# MCU.net
KiCad netlist of a schematic drawn in Altium Designer
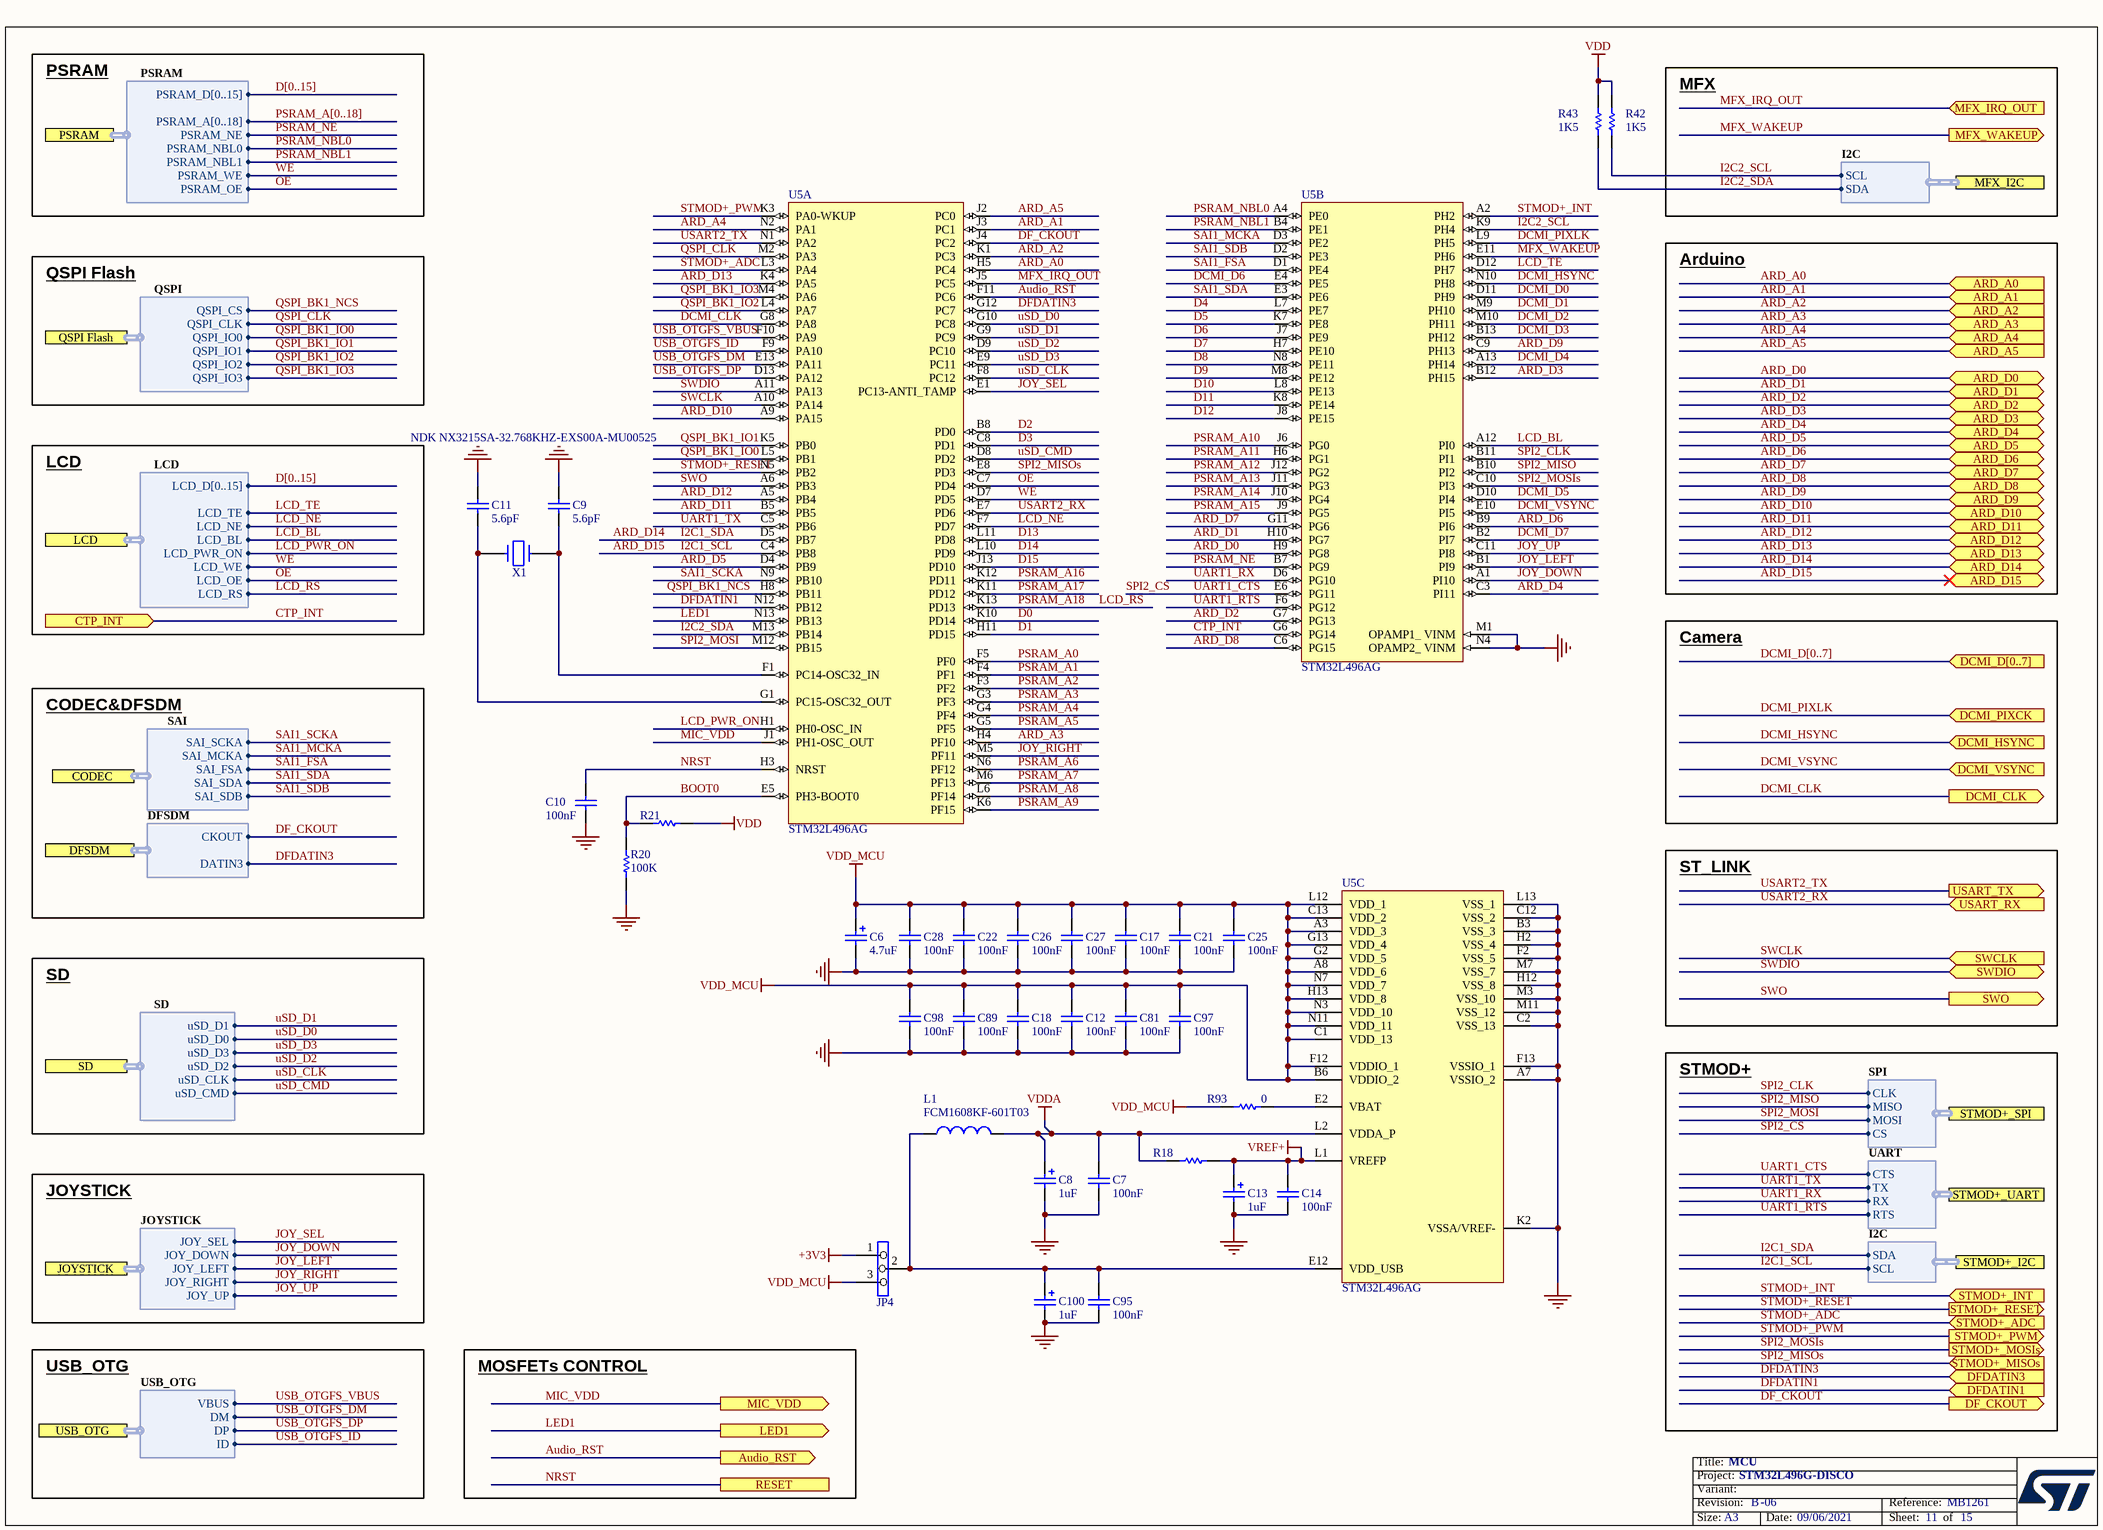
[diagram p0: MCU.SchDoc]

(export (version "E")
  (design (tool "Eeschema 10.0.6"))
  (components
    (comp (ref "C6")
      (value "4.7uF")
      (footprint "TAN-A")
      (description "TAN Capacitor,4.7uF,10%,16V,A Type,AVX")
      (fields (field (name "Comment") "TAJA475K016R") (field (name "PUBLISHER") "Altium Limited"))
      (libsource (lib "Miscellaneous Devices") (part "Cap Pol1"))
    )
    (comp (ref "C7")
      (value "100nF")
      (footprint "0603C")
      (description "Capacitor,100nF,10%,16V,X7R,0603,YAGEO")
      (fields (field (name "Comment") "CC0603KRX7R7BB104") (field (name "PUBLISHER") "Altium Limited"))
      (libsource (lib "Miscellaneous Devices") (part "Cap"))
    )
    (comp (ref "C8")
      (value "1uF")
      (footprint "TAN-A")
      (description "Tan Capacitor,1uF,10%,16V,Tan-A,TAJA105K016R")
      (fields (field (name "Comment") "TAJA105K016R") (field (name "PUBLISHER") "Altium Limited"))
      (libsource (lib "Miscellaneous Devices") (part "Cap Pol1"))
    )
    (comp (ref "C9")
      (value "5.6pF")
      (footprint "0603C")
      (description "Capacitor,5.6pF,0.25P,50V,NPO,0603")
      (fields (field (name "PUBLISHER") "Altium Limited"))
      (libsource (lib "Miscellaneous Devices") (part "Cap"))
    )
    (comp (ref "C10")
      (value "100nF")
      (footprint "0603C")
      (description "Capacitor,100nF,10%,16V,X7R,0603,YAGEO")
      (fields (field (name "Comment") "CC0603KRX7R7BB104") (field (name "PUBLISHER") "Altium Limited"))
      (libsource (lib "Miscellaneous Devices") (part "Cap"))
    )
    (comp (ref "C11")
      (value "5.6pF")
      (footprint "0603C")
      (description "Capacitor,5.6pF,0.25P,50V,NPO,0603")
      (fields (field (name "PUBLISHER") "Altium Limited"))
      (libsource (lib "Miscellaneous Devices") (part "Cap"))
    )
    (comp (ref "C12")
      (value "100nF")
      (footprint "0603C")
      (description "Capacitor,100nF,10%,16V,X7R,0603,YAGEO")
      (fields (field (name "Comment") "CC0603KRX7R7BB104") (field (name "PUBLISHER") "Altium Limited"))
      (libsource (lib "Miscellaneous Devices") (part "Cap"))
    )
    (comp (ref "C13")
      (value "1uF")
      (footprint "TAN-A")
      (description "Tan Capacitor,1uF,10%,16V,Tan-A,TAJA105K016R")
      (fields (field (name "Comment") "TAJA105K016R") (field (name "PUBLISHER") "Altium Limited"))
      (libsource (lib "Miscellaneous Devices") (part "Cap Pol1"))
    )
    (comp (ref "C14")
      (value "100nF")
      (footprint "0603C")
      (description "Capacitor,100nF,10%,16V,X7R,0603,YAGEO")
      (fields (field (name "Comment") "CC0603KRX7R7BB104") (field (name "PUBLISHER") "Altium Limited"))
      (libsource (lib "Miscellaneous Devices") (part "Cap"))
    )
    (comp (ref "C17")
      (value "100nF")
      (footprint "0603C")
      (description "Capacitor,100nF,10%,16V,X7R,0603,YAGEO")
      (fields (field (name "Comment") "CC0603KRX7R7BB104") (field (name "PUBLISHER") "Altium Limited"))
      (libsource (lib "Miscellaneous Devices") (part "Cap"))
    )
    (comp (ref "C18")
      (value "100nF")
      (footprint "0603C")
      (description "Capacitor,100nF,10%,16V,X7R,0603,YAGEO")
      (fields (field (name "Comment") "CC0603KRX7R7BB104") (field (name "PUBLISHER") "Altium Limited"))
      (libsource (lib "Miscellaneous Devices") (part "Cap"))
    )
    (comp (ref "C21")
      (value "100nF")
      (footprint "0603C")
      (description "Capacitor,100nF,10%,16V,X7R,0603,YAGEO")
      (fields (field (name "Comment") "CC0603KRX7R7BB104") (field (name "PUBLISHER") "Altium Limited"))
      (libsource (lib "Miscellaneous Devices") (part "Cap"))
    )
    (comp (ref "C22")
      (value "100nF")
      (footprint "0603C")
      (description "Capacitor,100nF,10%,16V,X7R,0603,YAGEO")
      (fields (field (name "Comment") "CC0603KRX7R7BB104") (field (name "PUBLISHER") "Altium Limited"))
      (libsource (lib "Miscellaneous Devices") (part "Cap"))
    )
    (comp (ref "C25")
      (value "100nF")
      (footprint "0603C")
      (description "Capacitor,100nF,10%,16V,X7R,0603,YAGEO")
      (fields (field (name "Comment") "CC0603KRX7R7BB104") (field (name "PUBLISHER") "Altium Limited"))
      (libsource (lib "Miscellaneous Devices") (part "Cap"))
    )
    (comp (ref "C26")
      (value "100nF")
      (footprint "0603C")
      (description "Capacitor,100nF,10%,16V,X7R,0603,YAGEO")
      (fields (field (name "Comment") "CC0603KRX7R7BB104") (field (name "PUBLISHER") "Altium Limited"))
      (libsource (lib "Miscellaneous Devices") (part "Cap"))
    )
    (comp (ref "C27")
      (value "100nF")
      (footprint "0603C")
      (description "Capacitor,100nF,10%,16V,X7R,0603,YAGEO")
      (fields (field (name "Comment") "CC0603KRX7R7BB104") (field (name "PUBLISHER") "Altium Limited"))
      (libsource (lib "Miscellaneous Devices") (part "Cap"))
    )
    (comp (ref "C28")
      (value "100nF")
      (footprint "0603C")
      (description "Capacitor,100nF,10%,16V,X7R,0603,YAGEO")
      (fields (field (name "Comment") "CC0603KRX7R7BB104") (field (name "PUBLISHER") "Altium Limited"))
      (libsource (lib "Miscellaneous Devices") (part "Cap"))
    )
    (comp (ref "C81")
      (value "100nF")
      (footprint "0603C")
      (description "Capacitor,100nF,10%,16V,X7R,0603,YAGEO")
      (fields (field (name "Comment") "CC0603KRX7R7BB104") (field (name "PUBLISHER") "Altium Limited"))
      (libsource (lib "Miscellaneous Devices") (part "Cap"))
    )
    (comp (ref "C89")
      (value "100nF")
      (footprint "0603C")
      (description "Capacitor,100nF,10%,16V,X7R,0603,YAGEO")
      (fields (field (name "Comment") "CC0603KRX7R7BB104") (field (name "PUBLISHER") "Altium Limited"))
      (libsource (lib "Miscellaneous Devices") (part "Cap"))
    )
    (comp (ref "C95")
      (value "100nF")
      (footprint "0603C")
      (description "Capacitor,100nF,10%,16V,X7R,0603,YAGEO")
      (fields (field (name "Comment") "CC0603KRX7R7BB104") (field (name "PUBLISHER") "Altium Limited"))
      (libsource (lib "Miscellaneous Devices") (part "Cap"))
    )
    (comp (ref "C97")
      (value "100nF")
      (footprint "0603C")
      (description "Capacitor,100nF,10%,16V,X7R,0603,YAGEO")
      (fields (field (name "Comment") "CC0603KRX7R7BB104") (field (name "PUBLISHER") "Altium Limited"))
      (libsource (lib "Miscellaneous Devices") (part "Cap"))
    )
    (comp (ref "C98")
      (value "100nF")
      (footprint "0603C")
      (description "Capacitor,100nF,10%,16V,X7R,0603,YAGEO")
      (fields (field (name "Comment") "CC0603KRX7R7BB104") (field (name "PUBLISHER") "Altium Limited"))
      (libsource (lib "Miscellaneous Devices") (part "Cap"))
    )
    (comp (ref "C100")
      (value "1uF")
      (footprint "TAN-A")
      (description "Tan Capacitor,1uF,10%,16V,Tan-A,TAJA105K016R")
      (fields (field (name "Comment") "TAJA105K016R") (field (name "PUBLISHER") "Altium Limited"))
      (libsource (lib "Miscellaneous Devices") (part "Cap Pol1"))
    )
    (comp (ref "JP4") (value "Jumper3") (footprint "SIP3") (libsource (lib "STR910_SCHLIB") (part "Jumper3")))
    (comp (ref "L1")
      (value "FCM1608KF-601T03")
      (footprint "0603L")
      (description "100uH Bead")
      (fields (field (name "PUBLISHER") "Altium Limited"))
      (libsource (lib "Miscellaneous Devices") (part "Inductor"))
    )
    (comp (ref "R18")
      (value "~")
      (footprint "0603R")
      (description "Resistor, 0 ,0603,1%,YAGEO")
      (fields (field (name "PUBLISHER") "Altium Limited"))
      (libsource (lib "Miscellaneous Devices") (part "res1"))
    )
    (comp (ref "R20")
      (value "100K")
      (footprint "0603R")
      (description "Resistor,100K,0603,1%,YAGEO")
      (fields (field (name "Comment") "RC0603FR-07100KL") (field (name "PUBLISHER") "Altium Limited"))
      (libsource (lib "Miscellaneous Devices") (part "res1"))
    )
    (comp (ref "R21")
      (value "~")
      (footprint "0603R")
      (description "Resistor,100K,0603,1%,YAGEO")
      (fields (field (name "PUBLISHER") "Altium Limited"))
      (libsource (lib "Miscellaneous Devices") (part "res1"))
    )
    (comp (ref "R42")
      (value "1K5")
      (footprint "0603R")
      (description "Resistor,1.5K,0603,1%,YAGEO")
      (fields (field (name "Comment") "RC0603FR-071K5L") (field (name "PUBLISHER") "Altium Limited"))
      (libsource (lib "Miscellaneous Devices") (part "res1"))
    )
    (comp (ref "R43")
      (value "1K5")
      (footprint "0603R")
      (description "Resistor,1.5K,0603,1%,YAGEO")
      (fields (field (name "Comment") "RC0603FR-071K5L") (field (name "PUBLISHER") "Altium Limited"))
      (libsource (lib "Miscellaneous Devices") (part "res1"))
    )
    (comp (ref "R93")
      (value "0")
      (footprint "0603R")
      (description "Resistor, 0 ,0603,1%,YAGEO")
      (fields (field (name "Comment") "RC0603JR-070RL") (field (name "PUBLISHER") "Altium Limited"))
      (libsource (lib "Miscellaneous Devices") (part "res1"))
    )
    (comp (ref "U5")
      (value "STM32L496AG")
      (footprint "FBGA169_0R5_7X7")
      (libsource (lib "Big Orca") (part "STM32L496G"))
    )
    (comp (ref "X1")
      (value "NDK NX3215SA-32.768KHZ-EXS00A-MU00525")
      (footprint "XTAL_2SM_3R2X1R5")
      (description "32.768kHz Crystal")
      (libsource (lib "MB1167") (part "CRYSTAL_32K"))
    )
  )
  (nets
    (net (code "12") (name "+3V3") (class "Default") (node (ref "JP4") (pin "1") (pintype "passive")))
    (net (code "13") (name "/ARD_A0") (class "Default")
      (node (ref "U5") (pin "H5") (pinfunction "PC4_H5") (pintype "bidirectional"))
    )
    (net (code "14") (name "/ARD_A1") (class "Default")
      (node (ref "U5") (pin "J3") (pinfunction "PC1_J3") (pintype "bidirectional"))
    )
    (net (code "15") (name "/ARD_A2") (class "Default")
      (node (ref "U5") (pin "K1") (pinfunction "PC3_K1") (pintype "bidirectional"))
    )
    (net (code "16") (name "/ARD_A3") (class "Default")
      (node (ref "U5") (pin "H4") (pinfunction "PF10_H4") (pintype "bidirectional"))
    )
    (net (code "17") (name "/ARD_A4") (class "Default")
      (node (ref "U5") (pin "N2") (pinfunction "PA1_N2") (pintype "bidirectional"))
    )
    (net (code "18") (name "/ARD_A5") (class "Default")
      (node (ref "U5") (pin "J2") (pinfunction "PC0_J2") (pintype "bidirectional"))
    )
    (net (code "19") (name "/ARD_D0") (class "Default")
      (node (ref "U5") (pin "H9") (pinfunction "PG8_H9") (pintype "bidirectional"))
    )
    (net (code "20") (name "/ARD_D1") (class "Default")
      (node (ref "U5") (pin "H10") (pinfunction "PG7_H10") (pintype "bidirectional"))
    )
    (net (code "21") (name "/ARD_D2") (class "Default")
      (node (ref "U5") (pin "G7") (pinfunction "PG13_G7") (pintype "bidirectional"))
    )
    (net (code "22") (name "/ARD_D3") (class "Default")
      (node (ref "U5") (pin "B12") (pinfunction "PH15_B12") (pintype "bidirectional"))
    )
    (net (code "23") (name "/ARD_D4") (class "Default")
      (node (ref "U5") (pin "C3") (pinfunction "PI11_C3") (pintype "bidirectional"))
    )
    (net (code "24") (name "/ARD_D5") (class "Default")
      (node (ref "U5") (pin "D4") (pinfunction "PB9_D4") (pintype "bidirectional"))
    )
    (net (code "25") (name "/ARD_D6") (class "Default")
      (node (ref "U5") (pin "B9") (pinfunction "PI6_B9") (pintype "bidirectional"))
    )
    (net (code "26") (name "/ARD_D7") (class "Default")
      (node (ref "U5") (pin "G11") (pinfunction "PG6_G11") (pintype "bidirectional"))
    )
    (net (code "27") (name "/ARD_D8") (class "Default")
      (node (ref "U5") (pin "C6") (pinfunction "PG15_C6") (pintype "bidirectional"))
    )
    (net (code "28") (name "/ARD_D9") (class "Default")
      (node (ref "U5") (pin "C9") (pinfunction "PH13_C9") (pintype "bidirectional"))
    )
    (net (code "29") (name "/ARD_D10") (class "Default")
      (node (ref "U5") (pin "A9") (pinfunction "PA15_A9") (pintype "bidirectional"))
    )
    (net (code "30") (name "/ARD_D11") (class "Default")
      (node (ref "U5") (pin "B5") (pinfunction "PB5_B5") (pintype "bidirectional"))
    )
    (net (code "31") (name "/ARD_D12") (class "Default")
      (node (ref "U5") (pin "A5") (pinfunction "PB4_A5") (pintype "bidirectional"))
    )
    (net (code "32") (name "/ARD_D13") (class "Default")
      (node (ref "U5") (pin "K4") (pinfunction "PA5_K4") (pintype "bidirectional"))
    )
    (net (code "33") (name "/ARD_D14") (class "Default")
      (node (ref "U5") (pin "D5") (pinfunction "PB7_D5") (pintype "bidirectional"))
    )
    (net (code "34") (name "/ARD_D15") (class "Default")
      (node (ref "U5") (pin "C4") (pinfunction "PB8_C4") (pintype "bidirectional+no_connect"))
    )
    (net (code "35") (name "/Audio_RST") (class "Default")
      (node (ref "U5") (pin "F11") (pinfunction "PC6_F11") (pintype "bidirectional"))
    )
    (net (code "36") (name "/BOOT0") (class "Default")
      (node (ref "R20") (pin "2") (pinfunction "2_2") (pintype "passive"))
      (node (ref "R21") (pin "2") (pinfunction "2_2") (pintype "passive"))
      (node (ref "U5") (pin "E5") (pinfunction "PH3-BOOT0_E5") (pintype "bidirectional"))
    )
    (net (code "37") (name "/CTP_INT") (class "Default")
      (node (ref "U5") (pin "G6") (pinfunction "PG14_G6") (pintype "bidirectional"))
    )
    (net (code "38") (name "/D0") (class "Default")
      (node (ref "U5") (pin "K10") (pinfunction "PD14_K10") (pintype "bidirectional"))
    )
    (net (code "39") (name "/D1") (class "Default")
      (node (ref "U5") (pin "H11") (pinfunction "PD15_H11") (pintype "bidirectional"))
    )
    (net (code "40") (name "/D2") (class "Default")
      (node (ref "U5") (pin "B8") (pinfunction "PD0_B8") (pintype "bidirectional"))
    )
    (net (code "41") (name "/D3") (class "Default")
      (node (ref "U5") (pin "C8") (pinfunction "PD1_C8") (pintype "bidirectional"))
    )
    (net (code "42") (name "/D4") (class "Default")
      (node (ref "U5") (pin "L7") (pinfunction "PE7_L7") (pintype "bidirectional"))
    )
    (net (code "43") (name "/D5") (class "Default")
      (node (ref "U5") (pin "K7") (pinfunction "PE8_K7") (pintype "bidirectional"))
    )
    (net (code "44") (name "/D6") (class "Default")
      (node (ref "U5") (pin "J7") (pinfunction "PE9_J7") (pintype "bidirectional"))
    )
    (net (code "45") (name "/D7") (class "Default")
      (node (ref "U5") (pin "H7") (pinfunction "PE10_H7") (pintype "bidirectional"))
    )
    (net (code "46") (name "/D8") (class "Default")
      (node (ref "U5") (pin "N8") (pinfunction "PE11_N8") (pintype "bidirectional"))
    )
    (net (code "47") (name "/D9") (class "Default")
      (node (ref "U5") (pin "M8") (pinfunction "PE12_M8") (pintype "bidirectional"))
    )
    (net (code "48") (name "/D10") (class "Default")
      (node (ref "U5") (pin "L8") (pinfunction "PE13_L8") (pintype "bidirectional"))
    )
    (net (code "49") (name "/D11") (class "Default")
      (node (ref "U5") (pin "K8") (pinfunction "PE14_K8") (pintype "bidirectional"))
    )
    (net (code "50") (name "/D12") (class "Default")
      (node (ref "U5") (pin "J8") (pinfunction "PE15_J8") (pintype "bidirectional"))
    )
    (net (code "51") (name "/D13") (class "Default")
      (node (ref "U5") (pin "L11") (pinfunction "PD8_L11") (pintype "bidirectional"))
    )
    (net (code "52") (name "/D14") (class "Default")
      (node (ref "U5") (pin "L10") (pinfunction "PD9_L10") (pintype "bidirectional"))
    )
    (net (code "53") (name "/D15") (class "Default")
      (node (ref "U5") (pin "J13") (pinfunction "PD10_J13") (pintype "bidirectional"))
    )
    (net (code "54") (name "/DCMI_CLK") (class "Default")
      (node (ref "U5") (pin "G8") (pinfunction "PA8_G8") (pintype "bidirectional"))
    )
    (net (code "55") (name "/DCMI_D0") (class "Default")
      (node (ref "U5") (pin "D11") (pinfunction "PH9_D11") (pintype "bidirectional"))
    )
    (net (code "56") (name "/DCMI_D1") (class "Default")
      (node (ref "U5") (pin "M9") (pinfunction "PH10_M9") (pintype "bidirectional"))
    )
    (net (code "57") (name "/DCMI_D2") (class "Default")
      (node (ref "U5") (pin "M10") (pinfunction "PH11_M10") (pintype "bidirectional"))
    )
    (net (code "58") (name "/DCMI_D3") (class "Default")
      (node (ref "U5") (pin "B13") (pinfunction "PH12_B13") (pintype "bidirectional"))
    )
    (net (code "59") (name "/DCMI_D4") (class "Default")
      (node (ref "U5") (pin "A13") (pinfunction "PH14_A13") (pintype "bidirectional"))
    )
    (net (code "60") (name "/DCMI_D5") (class "Default")
      (node (ref "U5") (pin "D10") (pinfunction "PI4_D10") (pintype "bidirectional"))
    )
    (net (code "61") (name "/DCMI_D6") (class "Default")
      (node (ref "U5") (pin "E4") (pinfunction "PE5_E4") (pintype "bidirectional"))
    )
    (net (code "62") (name "/DCMI_D7") (class "Default")
      (node (ref "U5") (pin "B2") (pinfunction "PI7_B2") (pintype "bidirectional"))
    )
    (net (code "64") (name "/DCMI_HSYNC") (class "Default")
      (node (ref "U5") (pin "N10") (pinfunction "PH8_N10") (pintype "bidirectional"))
    )
    (net (code "65") (name "/DCMI_PIXLK") (class "Default")
      (node (ref "U5") (pin "L9") (pinfunction "PH5_L9") (pintype "bidirectional"))
    )
    (net (code "66") (name "/DCMI_VSYNC") (class "Default")
      (node (ref "U5") (pin "E10") (pinfunction "PI5_E10") (pintype "bidirectional"))
    )
    (net (code "67") (name "/DFDATIN1") (class "Default")
      (node (ref "U5") (pin "N12") (pinfunction "PB12_N12") (pintype "bidirectional"))
    )
    (net (code "68") (name "/DFDATIN3") (class "Default")
      (node (ref "U5") (pin "G12") (pinfunction "PC7_G12") (pintype "bidirectional"))
    )
    (net (code "69") (name "/DF_CKOUT") (class "Default")
      (node (ref "U5") (pin "J4") (pinfunction "PC2_J4") (pintype "bidirectional"))
    )
    (net (code "71") (name "/I2C2_SCL") (class "Default")
      (node (ref "R42") (pin "2") (pinfunction "2_2") (pintype "passive"))
      (node (ref "U5") (pin "K9") (pinfunction "PH4_K9") (pintype "bidirectional"))
    )
    (net (code "72") (name "/I2C2_SDA") (class "Default")
      (node (ref "R43") (pin "2") (pinfunction "2_2") (pintype "passive"))
      (node (ref "U5") (pin "M13") (pinfunction "PB14_M13") (pintype "bidirectional"))
    )
    (net (code "73") (name "/JOY_DOWN") (class "Default")
      (node (ref "U5") (pin "A1") (pinfunction "PI10_A1") (pintype "bidirectional"))
    )
    (net (code "74") (name "/JOY_LEFT") (class "Default")
      (node (ref "U5") (pin "B1") (pinfunction "PI9_B1") (pintype "bidirectional"))
    )
    (net (code "75") (name "/JOY_RIGHT") (class "Default")
      (node (ref "U5") (pin "M5") (pinfunction "PF11_M5") (pintype "bidirectional"))
    )
    (net (code "76") (name "/JOY_SEL") (class "Default")
      (node (ref "U5") (pin "E1") (pinfunction "PC13-ANTI_TAMP_E1") (pintype "bidirectional"))
    )
    (net (code "77") (name "/JOY_UP") (class "Default")
      (node (ref "U5") (pin "C11") (pinfunction "PI8_C11") (pintype "bidirectional"))
    )
    (net (code "78") (name "/LCD_BL") (class "Default")
      (node (ref "U5") (pin "A12") (pinfunction "PI0_A12") (pintype "bidirectional"))
    )
    (net (code "79") (name "/LCD_NE") (class "Default")
      (node (ref "U5") (pin "F7") (pinfunction "PD7_F7") (pintype "bidirectional"))
    )
    (net (code "80") (name "/LCD_PWR_ON") (class "Default")
      (node (ref "U5") (pin "H1") (pinfunction "PH0-OSC_IN_H1") (pintype "bidirectional"))
    )
    (net (code "81") (name "/LCD_RS") (class "Default")
      (node (ref "U5") (pin "K13") (pinfunction "PD13_K13") (pintype "bidirectional"))
    )
    (net (code "82") (name "/LCD_TE") (class "Default")
      (node (ref "U5") (pin "D12") (pinfunction "PH7_D12") (pintype "bidirectional"))
    )
    (net (code "84") (name "/LED1") (class "Default")
      (node (ref "U5") (pin "N13") (pinfunction "PB13_N13") (pintype "bidirectional"))
    )
    (net (code "85") (name "/MFX_IRQ_OUT") (class "Default")
      (node (ref "U5") (pin "J5") (pinfunction "PC5_J5") (pintype "bidirectional"))
    )
    (net (code "86") (name "/MFX_WAKEUP") (class "Default")
      (node (ref "U5") (pin "E11") (pinfunction "PH6_E11") (pintype "bidirectional"))
    )
    (net (code "87") (name "/MIC_VDD") (class "Default")
      (node (ref "U5") (pin "J1") (pinfunction "PH1-OSC_OUT_J1") (pintype "bidirectional"))
    )
    (net (code "88") (name "/NRST") (class "Default")
      (node (ref "C10") (pin "1") (pinfunction "1_1") (pintype "passive"))
      (node (ref "U5") (pin "H3") (pinfunction "NRST_H3") (pintype "bidirectional"))
    )
    (net (code "89") (name "/OE") (class "Default")
      (node (ref "U5") (pin "C7") (pinfunction "PD4_C7") (pintype "bidirectional"))
    )
    (net (code "90") (name "/PSRAM_A0") (class "Default")
      (node (ref "U5") (pin "F5") (pinfunction "PF0_F5") (pintype "bidirectional"))
    )
    (net (code "91") (name "/PSRAM_A1") (class "Default")
      (node (ref "U5") (pin "F4") (pinfunction "PF1_F4") (pintype "bidirectional"))
    )
    (net (code "92") (name "/PSRAM_A2") (class "Default")
      (node (ref "U5") (pin "F3") (pinfunction "PF2_F3") (pintype "bidirectional"))
    )
    (net (code "93") (name "/PSRAM_A3") (class "Default")
      (node (ref "U5") (pin "G3") (pinfunction "PF3_G3") (pintype "bidirectional"))
    )
    (net (code "94") (name "/PSRAM_A4") (class "Default")
      (node (ref "U5") (pin "G4") (pinfunction "PF4_G4") (pintype "bidirectional"))
    )
    (net (code "95") (name "/PSRAM_A5") (class "Default")
      (node (ref "U5") (pin "G5") (pinfunction "PF5_G5") (pintype "bidirectional"))
    )
    (net (code "96") (name "/PSRAM_A6") (class "Default")
      (node (ref "U5") (pin "N6") (pinfunction "PF12_N6") (pintype "bidirectional"))
    )
    (net (code "97") (name "/PSRAM_A7") (class "Default")
      (node (ref "U5") (pin "M6") (pinfunction "PF13_M6") (pintype "bidirectional"))
    )
    (net (code "98") (name "/PSRAM_A8") (class "Default")
      (node (ref "U5") (pin "L6") (pinfunction "PF14_L6") (pintype "bidirectional"))
    )
    (net (code "99") (name "/PSRAM_A9") (class "Default")
      (node (ref "U5") (pin "K6") (pinfunction "PF15_K6") (pintype "bidirectional"))
    )
    (net (code "100") (name "/PSRAM_A10") (class "Default")
      (node (ref "U5") (pin "J6") (pinfunction "PG0_J6") (pintype "bidirectional"))
    )
    (net (code "101") (name "/PSRAM_A11") (class "Default")
      (node (ref "U5") (pin "H6") (pinfunction "PG1_H6") (pintype "bidirectional"))
    )
    (net (code "102") (name "/PSRAM_A12") (class "Default")
      (node (ref "U5") (pin "J12") (pinfunction "PG2_J12") (pintype "bidirectional"))
    )
    (net (code "103") (name "/PSRAM_A13") (class "Default")
      (node (ref "U5") (pin "J11") (pinfunction "PG3_J11") (pintype "bidirectional"))
    )
    (net (code "104") (name "/PSRAM_A14") (class "Default")
      (node (ref "U5") (pin "J10") (pinfunction "PG4_J10") (pintype "bidirectional"))
    )
    (net (code "105") (name "/PSRAM_A15") (class "Default")
      (node (ref "U5") (pin "J9") (pinfunction "PG5_J9") (pintype "bidirectional"))
    )
    (net (code "106") (name "/PSRAM_A16") (class "Default")
      (node (ref "U5") (pin "K12") (pinfunction "PD11_K12") (pintype "bidirectional"))
    )
    (net (code "107") (name "/PSRAM_A17") (class "Default")
      (node (ref "U5") (pin "K11") (pinfunction "PD12_K11") (pintype "bidirectional"))
    )
    (net (code "108") (name "/PSRAM_NBL0") (class "Default")
      (node (ref "U5") (pin "A4") (pinfunction "PE0_A4") (pintype "bidirectional"))
    )
    (net (code "109") (name "/PSRAM_NBL1") (class "Default")
      (node (ref "U5") (pin "B4") (pinfunction "PE1_B4") (pintype "bidirectional"))
    )
    (net (code "110") (name "/PSRAM_NE") (class "Default")
      (node (ref "U5") (pin "B7") (pinfunction "PG9_B7") (pintype "bidirectional"))
    )
    (net (code "112") (name "/QSPI_BK1_IO0") (class "Default")
      (node (ref "U5") (pin "L5") (pinfunction "PB1_L5") (pintype "bidirectional"))
    )
    (net (code "113") (name "/QSPI_BK1_IO1") (class "Default")
      (node (ref "U5") (pin "K5") (pinfunction "PB0_K5") (pintype "bidirectional"))
    )
    (net (code "114") (name "/QSPI_BK1_IO2") (class "Default")
      (node (ref "U5") (pin "L4") (pinfunction "PA7_L4") (pintype "bidirectional"))
    )
    (net (code "115") (name "/QSPI_BK1_IO3") (class "Default")
      (node (ref "U5") (pin "M4") (pinfunction "PA6_M4") (pintype "bidirectional"))
    )
    (net (code "116") (name "/QSPI_BK1_NCS") (class "Default")
      (node (ref "U5") (pin "H8") (pinfunction "PB11_H8") (pintype "bidirectional"))
    )
    (net (code "117") (name "/QSPI_CLK") (class "Default")
      (node (ref "U5") (pin "M2") (pinfunction "PA3_M2") (pintype "bidirectional"))
    )
    (net (code "118") (name "/SAI1_FSA") (class "Default")
      (node (ref "U5") (pin "D1") (pinfunction "PE4_D1") (pintype "bidirectional"))
    )
    (net (code "119") (name "/SAI1_MCKA") (class "Default")
      (node (ref "U5") (pin "D3") (pinfunction "PE2_D3") (pintype "bidirectional"))
    )
    (net (code "120") (name "/SAI1_SCKA") (class "Default")
      (node (ref "U5") (pin "N9") (pinfunction "PB10_N9") (pintype "bidirectional"))
    )
    (net (code "121") (name "/SAI1_SDA") (class "Default")
      (node (ref "U5") (pin "E3") (pinfunction "PE6_E3") (pintype "bidirectional"))
    )
    (net (code "122") (name "/SAI1_SDB") (class "Default")
      (node (ref "U5") (pin "D2") (pinfunction "PE3_D2") (pintype "bidirectional"))
    )
    (net (code "123") (name "/SPI2_CLK") (class "Default")
      (node (ref "U5") (pin "B11") (pinfunction "PI1_B11") (pintype "bidirectional"))
    )
    (net (code "124") (name "/SPI2_CS") (class "Default")
      (node (ref "U5") (pin "E6") (pinfunction "PG11_E6") (pintype "bidirectional"))
    )
    (net (code "125") (name "/SPI2_MISO") (class "Default")
      (node (ref "U5") (pin "B10") (pinfunction "PI2_B10") (pintype "bidirectional"))
    )
    (net (code "126") (name "/SPI2_MISOs") (class "Default")
      (node (ref "U5") (pin "E8") (pinfunction "PD3_E8") (pintype "bidirectional"))
    )
    (net (code "127") (name "/SPI2_MOSI") (class "Default")
      (node (ref "U5") (pin "M12") (pinfunction "PB15_M12") (pintype "bidirectional"))
    )
    (net (code "128") (name "/SPI2_MOSIs") (class "Default")
      (node (ref "U5") (pin "C10") (pinfunction "PI3_C10") (pintype "bidirectional"))
    )
    (net (code "129") (name "/STMOD+_ADC") (class "Default")
      (node (ref "U5") (pin "L3") (pinfunction "PA4_L3") (pintype "bidirectional"))
    )
    (net (code "130") (name "/STMOD+_INT") (class "Default")
      (node (ref "U5") (pin "A2") (pinfunction "PH2_A2") (pintype "bidirectional"))
    )
    (net (code "131") (name "/STMOD+_PWM") (class "Default")
      (node (ref "U5") (pin "K3") (pinfunction "PA0-WKUP_K3") (pintype "bidirectional"))
    )
    (net (code "132") (name "/STMOD+_RESET") (class "Default")
      (node (ref "U5") (pin "N5") (pinfunction "PB2_N5") (pintype "bidirectional"))
    )
    (net (code "133") (name "/SWCLK") (class "Default")
      (node (ref "U5") (pin "A10") (pinfunction "PA14_A10") (pintype "bidirectional"))
    )
    (net (code "134") (name "/SWDIO") (class "Default")
      (node (ref "U5") (pin "A11") (pinfunction "PA13_A11") (pintype "bidirectional"))
    )
    (net (code "135") (name "/SWO") (class "Default")
      (node (ref "U5") (pin "A6") (pinfunction "PB3_A6") (pintype "bidirectional"))
    )
    (net (code "136") (name "/UART1_RTS") (class "Default")
      (node (ref "U5") (pin "F6") (pinfunction "PG12_F6") (pintype "bidirectional"))
    )
    (net (code "137") (name "/UART1_RX") (class "Default")
      (node (ref "U5") (pin "D6") (pinfunction "PG10_D6") (pintype "bidirectional"))
    )
    (net (code "138") (name "/UART1_TX") (class "Default")
      (node (ref "U5") (pin "C5") (pinfunction "PB6_C5") (pintype "bidirectional"))
    )
    (net (code "139") (name "/USART2_RX") (class "Default")
      (node (ref "U5") (pin "E7") (pinfunction "PD6_E7") (pintype "bidirectional"))
    )
    (net (code "140") (name "/USART2_TX") (class "Default")
      (node (ref "U5") (pin "N1") (pinfunction "PA2_N1") (pintype "bidirectional"))
    )
    (net (code "141") (name "/USB_OTGFS_DM") (class "Default")
      (node (ref "U5") (pin "E13") (pinfunction "PA11_E13") (pintype "bidirectional"))
    )
    (net (code "142") (name "/USB_OTGFS_DP") (class "Default")
      (node (ref "U5") (pin "D13") (pinfunction "PA12_D13") (pintype "bidirectional"))
    )
    (net (code "143") (name "/USB_OTGFS_ID") (class "Default")
      (node (ref "U5") (pin "F9") (pinfunction "PA10_F9") (pintype "bidirectional"))
    )
    (net (code "144") (name "/USB_OTGFS_VBUS") (class "Default")
      (node (ref "U5") (pin "F10") (pinfunction "PA9_F10") (pintype "bidirectional"))
    )
    (net (code "145") (name "/WE") (class "Default")
      (node (ref "U5") (pin "D7") (pinfunction "PD5_D7") (pintype "bidirectional"))
    )
    (net (code "146") (name "/uSD_CLK") (class "Default")
      (node (ref "U5") (pin "F8") (pinfunction "PC12_F8") (pintype "bidirectional"))
    )
    (net (code "147") (name "/uSD_CMD") (class "Default")
      (node (ref "U5") (pin "D8") (pinfunction "PD2_D8") (pintype "bidirectional"))
    )
    (net (code "148") (name "/uSD_D0") (class "Default")
      (node (ref "U5") (pin "G10") (pinfunction "PC8_G10") (pintype "bidirectional"))
    )
    (net (code "149") (name "/uSD_D1") (class "Default")
      (node (ref "U5") (pin "G9") (pinfunction "PC9_G9") (pintype "bidirectional"))
    )
    (net (code "150") (name "/uSD_D2") (class "Default")
      (node (ref "U5") (pin "D9") (pinfunction "PC10_D9") (pintype "bidirectional"))
    )
    (net (code "151") (name "/uSD_D3") (class "Default")
      (node (ref "U5") (pin "E9") (pinfunction "PC11_E9") (pintype "bidirectional"))
    )
    (net (code "163") (name "GND") (class "Default")
      (node (ref "C10") (pin "2") (pinfunction "2_2") (pintype "passive"))
      (node (ref "C100") (pin "2") (pinfunction "2_2") (pintype "passive"))
      (node (ref "C11") (pin "1") (pinfunction "1_1") (pintype "passive"))
      (node (ref "C12") (pin "2") (pinfunction "2_2") (pintype "passive"))
      (node (ref "C13") (pin "2") (pinfunction "2_2") (pintype "passive"))
      (node (ref "C14") (pin "2") (pinfunction "2_2") (pintype "passive"))
      (node (ref "C17") (pin "2") (pinfunction "2_2") (pintype "passive"))
      (node (ref "C18") (pin "2") (pinfunction "2_2") (pintype "passive"))
      (node (ref "C21") (pin "2") (pinfunction "2_2") (pintype "passive"))
      (node (ref "C22") (pin "2") (pinfunction "2_2") (pintype "passive"))
      (node (ref "C25") (pin "2") (pinfunction "2_2") (pintype "passive"))
      (node (ref "C26") (pin "2") (pinfunction "2_2") (pintype "passive"))
      (node (ref "C27") (pin "2") (pinfunction "2_2") (pintype "passive"))
      (node (ref "C28") (pin "2") (pinfunction "2_2") (pintype "passive"))
      (node (ref "C6") (pin "2") (pinfunction "2_2") (pintype "passive"))
      (node (ref "C7") (pin "2") (pinfunction "2_2") (pintype "passive"))
      (node (ref "C8") (pin "2") (pinfunction "2_2") (pintype "passive"))
      (node (ref "C81") (pin "2") (pinfunction "2_2") (pintype "passive"))
      (node (ref "C89") (pin "2") (pinfunction "2_2") (pintype "passive"))
      (node (ref "C9") (pin "1") (pinfunction "1_1") (pintype "passive"))
      (node (ref "C95") (pin "2") (pinfunction "2_2") (pintype "passive"))
      (node (ref "C97") (pin "2") (pinfunction "2_2") (pintype "passive"))
      (node (ref "C98") (pin "2") (pinfunction "2_2") (pintype "passive"))
      (node (ref "R20") (pin "1") (pinfunction "1_1") (pintype "passive"))
      (node (ref "U5") (pin "A7") (pinfunction "VSSIO_2_A7") (pintype "power_in"))
      (node (ref "U5") (pin "B3") (pinfunction "VSS_3_B3") (pintype "power_in"))
      (node (ref "U5") (pin "C12") (pinfunction "VSS_2_C12") (pintype "power_in"))
      (node (ref "U5") (pin "C2") (pinfunction "VSS_13_C2") (pintype "power_in"))
      (node (ref "U5") (pin "F13") (pinfunction "VSSIO_1_F13") (pintype "power_in"))
      (node (ref "U5") (pin "F2") (pinfunction "VSS_5_F2") (pintype "power_in"))
      (node (ref "U5") (pin "H12") (pinfunction "VSS_8_H12") (pintype "power_in"))
      (node (ref "U5") (pin "H2") (pinfunction "VSS_4_H2") (pintype "power_in"))
      (node (ref "U5") (pin "K2") (pinfunction "VSSA/VREF-_K2") (pintype "power_in"))
      (node (ref "U5") (pin "L13") (pinfunction "VSS_1_L13") (pintype "power_in"))
      (node (ref "U5") (pin "M1") (pinfunction "OPAMP1__VINM_M1") (pintype "input"))
      (node (ref "U5") (pin "M11") (pinfunction "VSS_12_M11") (pintype "power_in"))
      (node (ref "U5") (pin "M3") (pinfunction "VSS_10_M3") (pintype "power_in"))
      (node (ref "U5") (pin "M7") (pinfunction "VSS_7_M7") (pintype "power_in"))
      (node (ref "U5") (pin "N4") (pinfunction "OPAMP2__VINM_N4") (pintype "input"))
    )
    (net (code "164") (name "Net-(U5A-PC14-OSC32_IN)") (class "Default")
      (node (ref "C9") (pin "2") (pinfunction "2_2") (pintype "passive"))
      (node (ref "U5") (pin "F1") (pinfunction "PC14-OSC32_IN_F1") (pintype "bidirectional"))
      (node (ref "X1") (pin "1") (pinfunction "1_1") (pintype "passive"))
    )
    (net (code "165") (name "Net-(U5A-PC15-OSC32_OUT)") (class "Default")
      (node (ref "C11") (pin "2") (pinfunction "2_2") (pintype "passive"))
      (node (ref "U5") (pin "G1") (pinfunction "PC15-OSC32_OUT_G1") (pintype "bidirectional"))
      (node (ref "X1") (pin "2") (pinfunction "2_2") (pintype "passive"))
    )
    (net (code "166") (name "Net-(U5C-VBAT)") (class "Default")
      (node (ref "R93") (pin "1") (pinfunction "1_1") (pintype "passive"))
      (node (ref "U5") (pin "E2") (pinfunction "VBAT_E2") (pintype "power_in"))
    )
    (net (code "167") (name "Net-(U5C-VDD_USB)") (class "Default")
      (node (ref "C100") (pin "1") (pinfunction "1_1") (pintype "passive"))
      (node (ref "C95") (pin "1") (pinfunction "1_1") (pintype "passive"))
      (node (ref "JP4") (pin "2") (pintype "passive"))
      (node (ref "L1") (pin "1") (pinfunction "1_1") (pintype "passive"))
      (node (ref "U5") (pin "E12") (pinfunction "VDD_USB_E12") (pintype "power_in"))
    )
    (net (code "168") (name "VDD") (class "Default")
      (node (ref "R21") (pin "1") (pinfunction "1_1") (pintype "passive"))
      (node (ref "R42") (pin "1") (pinfunction "1_1") (pintype "passive"))
      (node (ref "R43") (pin "1") (pinfunction "1_1") (pintype "passive"))
    )
    (net (code "169") (name "VDDA") (class "Default")
      (node (ref "C7") (pin "1") (pinfunction "1_1") (pintype "passive"))
      (node (ref "C8") (pin "1") (pinfunction "1_1") (pintype "passive"))
      (node (ref "L1") (pin "2") (pinfunction "2_2") (pintype "passive"))
      (node (ref "R18") (pin "2") (pinfunction "2_2") (pintype "passive"))
      (node (ref "U5") (pin "L2") (pinfunction "VDDA_P_L2") (pintype "power_in"))
    )
    (net (code "170") (name "VDD_MCU") (class "Default")
      (node (ref "C12") (pin "1") (pinfunction "1_1") (pintype "passive"))
      (node (ref "C17") (pin "1") (pinfunction "1_1") (pintype "passive"))
      (node (ref "C18") (pin "1") (pinfunction "1_1") (pintype "passive"))
      (node (ref "C21") (pin "1") (pinfunction "1_1") (pintype "passive"))
      (node (ref "C22") (pin "1") (pinfunction "1_1") (pintype "passive"))
      (node (ref "C25") (pin "1") (pinfunction "1_1") (pintype "passive"))
      (node (ref "C26") (pin "1") (pinfunction "1_1") (pintype "passive"))
      (node (ref "C27") (pin "1") (pinfunction "1_1") (pintype "passive"))
      (node (ref "C28") (pin "1") (pinfunction "1_1") (pintype "passive"))
      (node (ref "C6") (pin "1") (pinfunction "1_1") (pintype "passive"))
      (node (ref "C81") (pin "1") (pinfunction "1_1") (pintype "passive"))
      (node (ref "C89") (pin "1") (pinfunction "1_1") (pintype "passive"))
      (node (ref "C97") (pin "1") (pinfunction "1_1") (pintype "passive"))
      (node (ref "C98") (pin "1") (pinfunction "1_1") (pintype "passive"))
      (node (ref "JP4") (pin "3") (pintype "passive"))
      (node (ref "R93") (pin "2") (pinfunction "2_2") (pintype "passive"))
      (node (ref "U5") (pin "A3") (pinfunction "VDD_3_A3") (pintype "power_in"))
      (node (ref "U5") (pin "A8") (pinfunction "VDD_6_A8") (pintype "power_in"))
      (node (ref "U5") (pin "B6") (pinfunction "VDDIO_2_B6") (pintype "power_in"))
      (node (ref "U5") (pin "C1") (pinfunction "VDD_13_C1") (pintype "power_in"))
      (node (ref "U5") (pin "C13") (pinfunction "VDD_2_C13") (pintype "power_in"))
      (node (ref "U5") (pin "F12") (pinfunction "VDDIO_1_F12") (pintype "power_in"))
      (node (ref "U5") (pin "G13") (pinfunction "VDD_4_G13") (pintype "power_in"))
      (node (ref "U5") (pin "G2") (pinfunction "VDD_5_G2") (pintype "power_in"))
      (node (ref "U5") (pin "H13") (pinfunction "VDD_8_H13") (pintype "power_in"))
      (node (ref "U5") (pin "L12") (pinfunction "VDD_1_L12") (pintype "power_in"))
      (node (ref "U5") (pin "N11") (pinfunction "VDD_11_N11") (pintype "power_in"))
      (node (ref "U5") (pin "N3") (pinfunction "VDD_10_N3") (pintype "power_in"))
      (node (ref "U5") (pin "N7") (pinfunction "VDD_7_N7") (pintype "power_in"))
    )
    (net (code "171") (name "VREF+") (class "Default")
      (node (ref "C13") (pin "1") (pinfunction "1_1") (pintype "passive"))
      (node (ref "C14") (pin "1") (pinfunction "1_1") (pintype "passive"))
      (node (ref "R18") (pin "1") (pinfunction "1_1") (pintype "passive"))
      (node (ref "U5") (pin "L1") (pinfunction "VREFP_L1") (pintype "power_in"))
    )
  )
)
